# ESP32_cw.net
KiCad netlist of a schematic drawn in Altium Designer
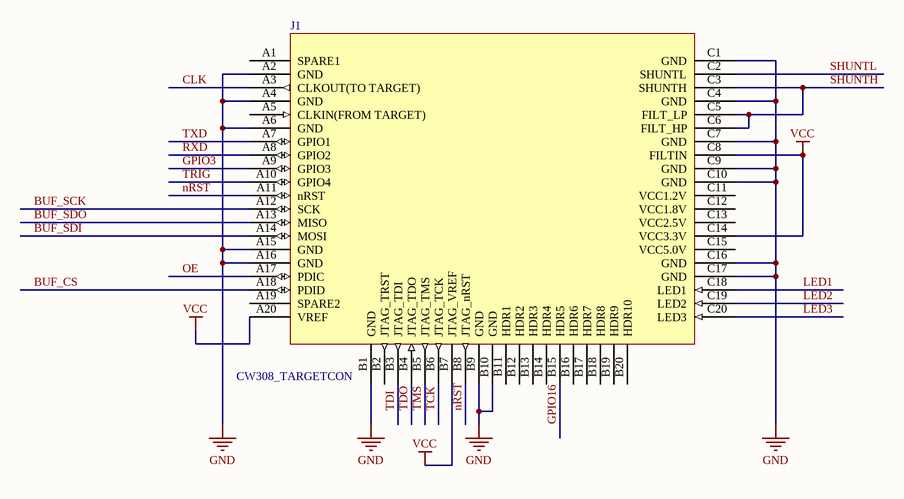
[diagram p0: ESP32_cw.SchDoc]

(export (version "E")
  (design (tool "Eeschema 10.0.6"))
  (components
    (comp (ref "J1")
      (value "CW308_TARGETCON")
      (footprint "CW308_TBOARD_CONN")
      (description "CW308 \"Standard\" Target Board Connector")
      (fields (field (name "PART NUMBER") "CW308_TBOARD"))
      (libsource (lib "NewAE_AltiumLib") (part "CW308_TBOARD"))
    )
  )
  (nets
    (net (code "1") (name "/BUF_CS") (class "Default")
      (node (ref "J1") (pin "A18") (pinfunction "PDID_A18") (pintype "bidirectional"))
    )
    (net (code "2") (name "/BUF_SCK") (class "Default")
      (node (ref "J1") (pin "A12") (pinfunction "SCK_A12") (pintype "bidirectional"))
    )
    (net (code "3") (name "/BUF_SDI") (class "Default")
      (node (ref "J1") (pin "A14") (pinfunction "MOSI_A14") (pintype "bidirectional"))
    )
    (net (code "4") (name "/BUF_SDO") (class "Default")
      (node (ref "J1") (pin "A13") (pinfunction "MISO_A13") (pintype "bidirectional"))
    )
    (net (code "5") (name "/CLK") (class "Default")
      (node (ref "J1") (pin "A3") (pinfunction "CLKOUT(TO_TARGET)_A3") (pintype "output"))
    )
    (net (code "6") (name "/GPIO3") (class "Default")
      (node (ref "J1") (pin "A9") (pinfunction "GPIO3_A9") (pintype "bidirectional"))
    )
    (net (code "7") (name "/GPIO16") (class "Default")
      (node (ref "J1") (pin "B15") (pinfunction "HDR5_B15") (pintype "passive"))
    )
    (net (code "8") (name "/LED1") (class "Default")
      (node (ref "J1") (pin "C18") (pinfunction "LED1_C18") (pintype "input"))
    )
    (net (code "9") (name "/LED2") (class "Default")
      (node (ref "J1") (pin "C19") (pinfunction "LED2_C19") (pintype "input"))
    )
    (net (code "10") (name "/LED3") (class "Default")
      (node (ref "J1") (pin "C20") (pinfunction "LED3_C20") (pintype "input"))
    )
    (net (code "11") (name "/OE") (class "Default")
      (node (ref "J1") (pin "A17") (pinfunction "PDIC_A17") (pintype "bidirectional"))
    )
    (net (code "12") (name "/RXD") (class "Default")
      (node (ref "J1") (pin "A8") (pinfunction "GPIO2_A8") (pintype "bidirectional"))
    )
    (net (code "13") (name "/SHUNTH") (class "Default")
      (node (ref "J1") (pin "C3") (pinfunction "SHUNTH_C3") (pintype "passive"))
      (node (ref "J1") (pin "C5") (pinfunction "FILT_LP_C5") (pintype "passive"))
      (node (ref "J1") (pin "C6") (pinfunction "FILT_HP_C6") (pintype "passive"))
    )
    (net (code "14") (name "/SHUNTL") (class "Default")
      (node (ref "J1") (pin "C2") (pinfunction "SHUNTL_C2") (pintype "passive"))
    )
    (net (code "15") (name "/TCK") (class "Default")
      (node (ref "J1") (pin "B6") (pinfunction "JTAG_TCK_B6") (pintype "output"))
    )
    (net (code "16") (name "/TDI") (class "Default")
      (node (ref "J1") (pin "B3") (pinfunction "JTAG_TDI_B3") (pintype "output"))
    )
    (net (code "17") (name "/TDO") (class "Default")
      (node (ref "J1") (pin "B4") (pinfunction "JTAG_TDO_B4") (pintype "input"))
    )
    (net (code "18") (name "/TMS") (class "Default")
      (node (ref "J1") (pin "B5") (pinfunction "JTAG_TMS_B5") (pintype "output"))
    )
    (net (code "19") (name "/TRIG") (class "Default")
      (node (ref "J1") (pin "A10") (pinfunction "GPIO4_A10") (pintype "bidirectional"))
    )
    (net (code "20") (name "/TXD") (class "Default")
      (node (ref "J1") (pin "A7") (pinfunction "GPIO1_A7") (pintype "bidirectional"))
    )
    (net (code "21") (name "/nRST") (class "Default")
      (node (ref "J1") (pin "A11") (pinfunction "nRST_A11") (pintype "bidirectional"))
      (node (ref "J1") (pin "B8") (pinfunction "JTAG_nRST_B8") (pintype "output"))
    )
    (net (code "22") (name "GND") (class "Default")
      (node (ref "J1") (pin "A15") (pinfunction "GND_A15") (pintype "passive"))
      (node (ref "J1") (pin "A16") (pinfunction "GND_A16") (pintype "passive"))
      (node (ref "J1") (pin "A2") (pinfunction "GND_A2") (pintype "passive"))
      (node (ref "J1") (pin "A4") (pinfunction "GND_A4") (pintype "passive"))
      (node (ref "J1") (pin "A6") (pinfunction "GND_A6") (pintype "power_in"))
      (node (ref "J1") (pin "B1") (pinfunction "GND_B1") (pintype "passive"))
      (node (ref "J1") (pin "B10") (pinfunction "GND_B10") (pintype "passive"))
      (node (ref "J1") (pin "B9") (pinfunction "GND_B9") (pintype "passive"))
      (node (ref "J1") (pin "C1") (pinfunction "GND_C1") (pintype "power_in"))
      (node (ref "J1") (pin "C10") (pinfunction "GND_C10") (pintype "power_in"))
      (node (ref "J1") (pin "C16") (pinfunction "GND_C16") (pintype "power_in"))
      (node (ref "J1") (pin "C17") (pinfunction "GND_C17") (pintype "power_in"))
      (node (ref "J1") (pin "C4") (pinfunction "GND_C4") (pintype "power_in"))
      (node (ref "J1") (pin "C7") (pinfunction "GND_C7") (pintype "power_in"))
      (node (ref "J1") (pin "C9") (pinfunction "GND_C9") (pintype "power_in"))
    )
    (net (code "23") (name "VCC") (class "Default")
      (node (ref "J1") (pin "A20") (pinfunction "VREF_A20") (pintype "tri_state"))
      (node (ref "J1") (pin "B7") (pinfunction "JTAG_VREF_B7") (pintype "tri_state"))
      (node (ref "J1") (pin "C14") (pinfunction "VCC3.3V_C14") (pintype "power_in"))
      (node (ref "J1") (pin "C8") (pinfunction "FILTIN_C8") (pintype "passive"))
    )
    (net (code "24") (name "unconnected-(J1-CLKIN(FROM_TARGET)-PadA5)") (class "Default")
      (node (ref "J1") (pin "A5") (pinfunction "CLKIN(FROM_TARGET)_A5") (pintype "input"))
    )
    (net (code "25") (name "unconnected-(J1-HDR1-PadB11)") (class "Default")
      (node (ref "J1") (pin "B11") (pinfunction "HDR1_B11") (pintype "passive"))
    )
    (net (code "26") (name "unconnected-(J1-HDR2-PadB12)") (class "Default")
      (node (ref "J1") (pin "B12") (pinfunction "HDR2_B12") (pintype "passive"))
    )
    (net (code "27") (name "unconnected-(J1-HDR3-PadB13)") (class "Default")
      (node (ref "J1") (pin "B13") (pinfunction "HDR3_B13") (pintype "passive"))
    )
    (net (code "28") (name "unconnected-(J1-HDR4-PadB14)") (class "Default")
      (node (ref "J1") (pin "B14") (pinfunction "HDR4_B14") (pintype "passive"))
    )
    (net (code "29") (name "unconnected-(J1-HDR6-PadB16)") (class "Default")
      (node (ref "J1") (pin "B16") (pinfunction "HDR6_B16") (pintype "passive"))
    )
    (net (code "30") (name "unconnected-(J1-HDR7-PadB17)") (class "Default")
      (node (ref "J1") (pin "B17") (pinfunction "HDR7_B17") (pintype "passive"))
    )
    (net (code "31") (name "unconnected-(J1-HDR8-PadB18)") (class "Default")
      (node (ref "J1") (pin "B18") (pinfunction "HDR8_B18") (pintype "passive"))
    )
    (net (code "32") (name "unconnected-(J1-HDR9-PadB19)") (class "Default")
      (node (ref "J1") (pin "B19") (pinfunction "HDR9_B19") (pintype "passive"))
    )
    (net (code "33") (name "unconnected-(J1-HDR10-PadB20)") (class "Default")
      (node (ref "J1") (pin "B20") (pinfunction "HDR10_B20") (pintype "passive"))
    )
    (net (code "34") (name "unconnected-(J1-JTAG_TRST-PadB2)") (class "Default")
      (node (ref "J1") (pin "B2") (pinfunction "JTAG_TRST_B2") (pintype "output"))
    )
    (net (code "35") (name "unconnected-(J1-SPARE1-PadA1)") (class "Default")
      (node (ref "J1") (pin "A1") (pinfunction "SPARE1_A1") (pintype "passive"))
    )
    (net (code "36") (name "unconnected-(J1-SPARE2-PadA19)") (class "Default")
      (node (ref "J1") (pin "A19") (pinfunction "SPARE2_A19") (pintype "passive"))
    )
    (net (code "37") (name "unconnected-(J1-VCC1.2V-PadC11)") (class "Default")
      (node (ref "J1") (pin "C11") (pinfunction "VCC1.2V_C11") (pintype "power_in"))
    )
    (net (code "38") (name "unconnected-(J1-VCC1.8V-PadC12)") (class "Default")
      (node (ref "J1") (pin "C12") (pinfunction "VCC1.8V_C12") (pintype "power_in"))
    )
    (net (code "39") (name "unconnected-(J1-VCC2.5V-PadC13)") (class "Default")
      (node (ref "J1") (pin "C13") (pinfunction "VCC2.5V_C13") (pintype "power_in"))
    )
    (net (code "40") (name "unconnected-(J1-VCC5.0V-PadC15)") (class "Default")
      (node (ref "J1") (pin "C15") (pinfunction "VCC5.0V_C15") (pintype "power_in"))
    )
  )
)
